# P27_v3.net
KiCad netlist of a schematic drawn in EAGLE
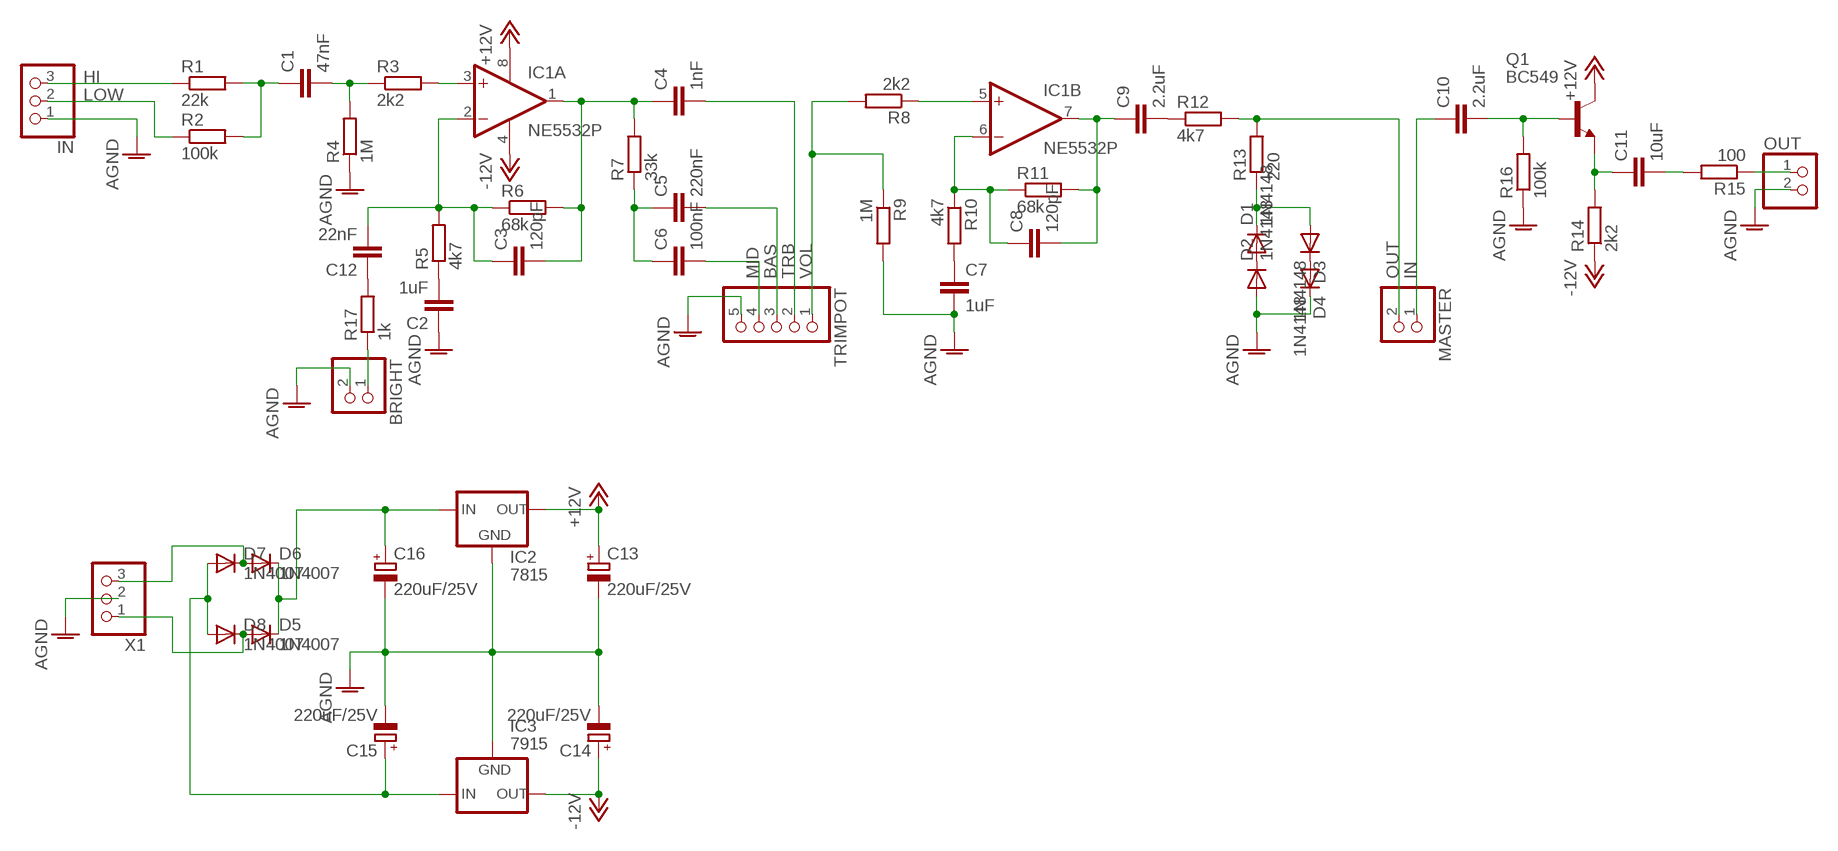
[diagram p0: schematic, sheet 1]

(export (version "E")
  (design (tool "Eeschema 10.0.6"))
  (components
    (comp (ref "BRIGHT")
      (value "PINHD-1X2")
      (footprint "eagle-import:1X02")
      (libsource (lib "eagle-import") (part "PINHD-1X2"))
    )
    (comp (ref "C1")
      (value "47nF")
      (footprint "eagle-import:C050-025X075")
      (libsource (lib "eagle-import") (part "C-EU050-025X075"))
    )
    (comp (ref "C2")
      (value "1uF")
      (footprint "eagle-import:C050-025X075")
      (libsource (lib "eagle-import") (part "C-EU050-025X075"))
    )
    (comp (ref "C3")
      (value "120pF")
      (footprint "eagle-import:C050-025X075")
      (libsource (lib "eagle-import") (part "C-EU050-025X075"))
    )
    (comp (ref "C4")
      (value "1nF")
      (footprint "eagle-import:C050-025X075")
      (libsource (lib "eagle-import") (part "C-EU050-025X075"))
    )
    (comp (ref "C5")
      (value "220nF")
      (footprint "eagle-import:C050-025X075")
      (libsource (lib "eagle-import") (part "C-EU050-025X075"))
    )
    (comp (ref "C6")
      (value "100nF")
      (footprint "eagle-import:C050-025X075")
      (libsource (lib "eagle-import") (part "C-EU050-025X075"))
    )
    (comp (ref "C7")
      (value "1uF")
      (footprint "eagle-import:C050-025X075")
      (libsource (lib "eagle-import") (part "C-EU050-025X075"))
    )
    (comp (ref "C8")
      (value "120pF")
      (footprint "eagle-import:C050-025X075")
      (libsource (lib "eagle-import") (part "C-EU050-025X075"))
    )
    (comp (ref "C9")
      (value "2.2uF")
      (footprint "eagle-import:C050-025X075")
      (libsource (lib "eagle-import") (part "C-EU050-025X075"))
    )
    (comp (ref "C10")
      (value "2.2uF")
      (footprint "eagle-import:C050-025X075")
      (libsource (lib "eagle-import") (part "C-EU050-025X075"))
    )
    (comp (ref "C11")
      (value "10uF")
      (footprint "eagle-import:C050-025X075")
      (libsource (lib "eagle-import") (part "C-EU050-025X075"))
    )
    (comp (ref "C12")
      (value "22nF")
      (footprint "eagle-import:C050-025X075")
      (libsource (lib "eagle-import") (part "C-EU050-025X075"))
    )
    (comp (ref "C13")
      (value "220uF/25V")
      (footprint "eagle-import:E2,5-6")
      (libsource (lib "eagle-import") (part "CPOL-EUE2.5-6"))
    )
    (comp (ref "C14")
      (value "220uF/25V")
      (footprint "eagle-import:E2,5-6")
      (libsource (lib "eagle-import") (part "CPOL-EUE2.5-6"))
    )
    (comp (ref "C15")
      (value "220uF/25V")
      (footprint "eagle-import:E2,5-6")
      (libsource (lib "eagle-import") (part "CPOL-EUE2.5-6"))
    )
    (comp (ref "C16")
      (value "220uF/25V")
      (footprint "eagle-import:E2,5-6")
      (libsource (lib "eagle-import") (part "CPOL-EUE2.5-6"))
    )
    (comp (ref "D1")
      (value "1N4148")
      (footprint "eagle-import:DO41-7")
      (libsource (lib "eagle-import") (part "1N4004D"))
    )
    (comp (ref "D2")
      (value "1N4148")
      (footprint "eagle-import:DO41-7")
      (libsource (lib "eagle-import") (part "1N4004D"))
    )
    (comp (ref "D3")
      (value "1N4148")
      (footprint "eagle-import:DO41-7")
      (libsource (lib "eagle-import") (part "1N4004D"))
    )
    (comp (ref "D4")
      (value "1N4148")
      (footprint "eagle-import:DO41-7")
      (libsource (lib "eagle-import") (part "1N4004D"))
    )
    (comp (ref "D5")
      (value "1N4007")
      (footprint "eagle-import:DO41-7")
      (libsource (lib "eagle-import") (part "1N4004D"))
    )
    (comp (ref "D6")
      (value "1N4007")
      (footprint "eagle-import:DO41-7")
      (libsource (lib "eagle-import") (part "1N4004D"))
    )
    (comp (ref "D7")
      (value "1N4007")
      (footprint "eagle-import:DO41-7")
      (libsource (lib "eagle-import") (part "1N4004D"))
    )
    (comp (ref "D8")
      (value "1N4007")
      (footprint "eagle-import:DO41-7")
      (libsource (lib "eagle-import") (part "1N4004D"))
    )
    (comp (ref "IC1")
      (value "NE5532P")
      (footprint "eagle-import:DIL08")
      (libsource (lib "eagle-import") (part "NE5532P"))
    )
    (comp (ref "IC2")
      (value "7815")
      (footprint "eagle-import:78XXS")
      (libsource (lib "eagle-import") (part "78XXTO-220"))
    )
    (comp (ref "IC3")
      (value "7915")
      (footprint "eagle-import:79XXS")
      (libsource (lib "eagle-import") (part "79XXTO-220"))
    )
    (comp (ref "IN")
      (value "PINHD-1X3180")
      (footprint "eagle-import:1X03")
      (libsource (lib "eagle-import") (part "PINHD-1X3180"))
    )
    (comp (ref "MASTER")
      (value "PINHD-1X2")
      (footprint "eagle-import:1X02")
      (libsource (lib "eagle-import") (part "PINHD-1X2"))
    )
    (comp (ref "OUT")
      (value "PINHD-1X2")
      (footprint "eagle-import:1X02")
      (libsource (lib "eagle-import") (part "PINHD-1X2"))
    )
    (comp (ref "Q1")
      (value "BC549")
      (footprint "eagle-import:TO92")
      (libsource (lib "eagle-import") (part "BC337"))
    )
    (comp (ref "R1")
      (value "22k")
      (footprint "eagle-import:0207_7")
      (libsource (lib "eagle-import") (part "R-EU_0207/7"))
    )
    (comp (ref "R2")
      (value "100k")
      (footprint "eagle-import:0207_7")
      (libsource (lib "eagle-import") (part "R-EU_0207/7"))
    )
    (comp (ref "R3")
      (value "2k2")
      (footprint "eagle-import:0207_7")
      (libsource (lib "eagle-import") (part "R-EU_0207/7"))
    )
    (comp (ref "R4")
      (value "1M")
      (footprint "eagle-import:0207_7")
      (libsource (lib "eagle-import") (part "R-EU_0207/7"))
    )
    (comp (ref "R5")
      (value "4k7")
      (footprint "eagle-import:0207_7")
      (libsource (lib "eagle-import") (part "R-EU_0207/7"))
    )
    (comp (ref "R6")
      (value "68k")
      (footprint "eagle-import:0207_7")
      (libsource (lib "eagle-import") (part "R-EU_0207/7"))
    )
    (comp (ref "R7")
      (value "33k")
      (footprint "eagle-import:0207_7")
      (libsource (lib "eagle-import") (part "R-EU_0207/7"))
    )
    (comp (ref "R8")
      (value "2k2")
      (footprint "eagle-import:0207_7")
      (libsource (lib "eagle-import") (part "R-EU_0207/7"))
    )
    (comp (ref "R9")
      (value "1M")
      (footprint "eagle-import:0207_7")
      (libsource (lib "eagle-import") (part "R-EU_0207/7"))
    )
    (comp (ref "R10")
      (value "4k7")
      (footprint "eagle-import:0207_7")
      (libsource (lib "eagle-import") (part "R-EU_0207/7"))
    )
    (comp (ref "R11")
      (value "68k")
      (footprint "eagle-import:0207_7")
      (libsource (lib "eagle-import") (part "R-EU_0207/7"))
    )
    (comp (ref "R12")
      (value "4k7")
      (footprint "eagle-import:0207_7")
      (libsource (lib "eagle-import") (part "R-EU_0207/7"))
    )
    (comp (ref "R13")
      (value "220")
      (footprint "eagle-import:0207_7")
      (libsource (lib "eagle-import") (part "R-EU_0207/7"))
    )
    (comp (ref "R14")
      (value "2k2")
      (footprint "eagle-import:0207_7")
      (libsource (lib "eagle-import") (part "R-EU_0207/7"))
    )
    (comp (ref "R15")
      (value "100")
      (footprint "eagle-import:0207_7")
      (libsource (lib "eagle-import") (part "R-EU_0207/7"))
    )
    (comp (ref "R16")
      (value "100k")
      (footprint "eagle-import:0207_7")
      (libsource (lib "eagle-import") (part "R-EU_0207/7"))
    )
    (comp (ref "R17")
      (value "1k")
      (footprint "eagle-import:0207_7")
      (libsource (lib "eagle-import") (part "R-EU_0207/7"))
    )
    (comp (ref "TRIMPOT")
      (value "PINHD-1X5")
      (footprint "eagle-import:1X05")
      (libsource (lib "eagle-import") (part "PINHD-1X5"))
    )
    (comp (ref "X1")
      (value "W237-103")
      (footprint "eagle-import:W237-103")
      (libsource (lib "eagle-import") (part "W237-103"))
    )
  )
  (nets
    (net (code "1") (name "+12V") (class "Default")
      (node (ref "C13") (pin "+") (pinfunction "+_+") (pintype "passive"))
      (node (ref "IC1") (pin "8") (pinfunction "V+_8") (pintype "power_in"))
      (node (ref "IC2") (pin "OUT") (pinfunction "OUT_OUT") (pintype "passive"))
      (node (ref "Q1") (pin "3") (pinfunction "C_3") (pintype "passive"))
    )
    (net (code "2") (name "-12V") (class "Default")
      (node (ref "C14") (pin "+") (pinfunction "+_+") (pintype "passive"))
      (node (ref "IC1") (pin "4") (pinfunction "V-_4") (pintype "power_in"))
      (node (ref "IC3") (pin "OUT") (pinfunction "OUT_OUT") (pintype "passive"))
      (node (ref "R14") (pin "1") (pinfunction "1_1") (pintype "passive"))
    )
    (net (code "3") (name "/BAS") (class "Default")
      (node (ref "C5") (pin "2") (pinfunction "2_2") (pintype "passive"))
      (node (ref "TRIMPOT") (pin "3") (pinfunction "3_3") (pintype "passive"))
    )
    (net (code "4") (name "/HI") (class "Default")
      (node (ref "IN") (pin "3") (pinfunction "3_3") (pintype "passive"))
      (node (ref "R1") (pin "1") (pinfunction "1_1") (pintype "passive"))
    )
    (net (code "5") (name "/IN") (class "Default")
      (node (ref "C10") (pin "1") (pinfunction "1_1") (pintype "passive"))
      (node (ref "MASTER") (pin "1") (pinfunction "1_1") (pintype "passive"))
    )
    (net (code "6") (name "/LOW") (class "Default")
      (node (ref "IN") (pin "2") (pinfunction "2_2") (pintype "passive"))
      (node (ref "R2") (pin "1") (pinfunction "1_1") (pintype "passive"))
    )
    (net (code "7") (name "/MID") (class "Default")
      (node (ref "C6") (pin "2") (pinfunction "2_2") (pintype "passive"))
      (node (ref "TRIMPOT") (pin "4") (pinfunction "4_4") (pintype "passive"))
    )
    (net (code "8") (name "/OUT") (class "Default")
      (node (ref "MASTER") (pin "2") (pinfunction "2_2") (pintype "passive"))
      (node (ref "R12") (pin "2") (pinfunction "2_2") (pintype "passive"))
      (node (ref "R13") (pin "2") (pinfunction "2_2") (pintype "passive"))
    )
    (net (code "9") (name "/TRB") (class "Default")
      (node (ref "C4") (pin "2") (pinfunction "2_2") (pintype "passive"))
      (node (ref "TRIMPOT") (pin "2") (pinfunction "2_2") (pintype "passive"))
    )
    (net (code "10") (name "/VOL") (class "Default")
      (node (ref "R8") (pin "2") (pinfunction "2_2") (pintype "passive"))
      (node (ref "R9") (pin "1") (pinfunction "1_1") (pintype "passive"))
      (node (ref "TRIMPOT") (pin "1") (pinfunction "1_1") (pintype "passive"))
    )
    (net (code "11") (name "AGND") (class "Default")
      (node (ref "BRIGHT") (pin "2") (pinfunction "2_2") (pintype "passive"))
      (node (ref "C13") (pin "-") (pinfunction "-_-") (pintype "passive"))
      (node (ref "C14") (pin "-") (pinfunction "-_-") (pintype "passive"))
      (node (ref "C15") (pin "-") (pinfunction "-_-") (pintype "passive"))
      (node (ref "C16") (pin "-") (pinfunction "-_-") (pintype "passive"))
      (node (ref "C2") (pin "1") (pinfunction "1_1") (pintype "passive"))
      (node (ref "C7") (pin "2") (pinfunction "2_2") (pintype "passive"))
      (node (ref "D2") (pin "A") (pinfunction "A_A") (pintype "passive"))
      (node (ref "D4") (pin "C") (pinfunction "C_C") (pintype "passive"))
      (node (ref "IC2") (pin "GND") (pinfunction "GND_GND") (pintype "input"))
      (node (ref "IC3") (pin "GND") (pinfunction "GND_GND") (pintype "input"))
      (node (ref "IN") (pin "1") (pinfunction "1_1") (pintype "passive"))
      (node (ref "OUT") (pin "2") (pinfunction "2_2") (pintype "passive"))
      (node (ref "R16") (pin "1") (pinfunction "1_1") (pintype "passive"))
      (node (ref "R4") (pin "1") (pinfunction "1_1") (pintype "passive"))
      (node (ref "R9") (pin "2") (pinfunction "2_2") (pintype "passive"))
      (node (ref "TRIMPOT") (pin "5") (pinfunction "5_5") (pintype "passive"))
      (node (ref "X1") (pin "2") (pinfunction "2_2") (pintype "passive"))
    )
    (net (code "12") (name "Net-(BRIGHT-Pad1)") (class "Default")
      (node (ref "BRIGHT") (pin "1") (pinfunction "1_1") (pintype "passive"))
      (node (ref "R17") (pin "1") (pinfunction "1_1") (pintype "passive"))
    )
    (net (code "13") (name "Net-(C1-Pad1)") (class "Default")
      (node (ref "C1") (pin "1") (pinfunction "1_1") (pintype "passive"))
      (node (ref "R1") (pin "2") (pinfunction "2_2") (pintype "passive"))
      (node (ref "R2") (pin "2") (pinfunction "2_2") (pintype "passive"))
    )
    (net (code "14") (name "Net-(C1-Pad2)") (class "Default")
      (node (ref "C1") (pin "2") (pinfunction "2_2") (pintype "passive"))
      (node (ref "R3") (pin "1") (pinfunction "1_1") (pintype "passive"))
      (node (ref "R4") (pin "2") (pinfunction "2_2") (pintype "passive"))
    )
    (net (code "15") (name "Net-(C2-Pad2)") (class "Default")
      (node (ref "C2") (pin "2") (pinfunction "2_2") (pintype "passive"))
      (node (ref "R5") (pin "1") (pinfunction "1_1") (pintype "passive"))
    )
    (net (code "16") (name "Net-(C5-Pad1)") (class "Default")
      (node (ref "C5") (pin "1") (pinfunction "1_1") (pintype "passive"))
      (node (ref "C6") (pin "1") (pinfunction "1_1") (pintype "passive"))
      (node (ref "R7") (pin "1") (pinfunction "1_1") (pintype "passive"))
    )
    (net (code "17") (name "Net-(C7-Pad1)") (class "Default")
      (node (ref "C7") (pin "1") (pinfunction "1_1") (pintype "passive"))
      (node (ref "R10") (pin "2") (pinfunction "2_2") (pintype "passive"))
    )
    (net (code "18") (name "Net-(C9-Pad2)") (class "Default")
      (node (ref "C9") (pin "2") (pinfunction "2_2") (pintype "passive"))
      (node (ref "R12") (pin "1") (pinfunction "1_1") (pintype "passive"))
    )
    (net (code "19") (name "Net-(C11-Pad2)") (class "Default")
      (node (ref "C11") (pin "2") (pinfunction "2_2") (pintype "passive"))
      (node (ref "R15") (pin "2") (pinfunction "2_2") (pintype "passive"))
    )
    (net (code "20") (name "Net-(C12-Pad1)") (class "Default")
      (node (ref "C12") (pin "1") (pinfunction "1_1") (pintype "passive"))
      (node (ref "R17") (pin "2") (pinfunction "2_2") (pintype "passive"))
    )
    (net (code "21") (name "Net-(C15-Pad+)") (class "Default")
      (node (ref "C15") (pin "+") (pinfunction "+_+") (pintype "passive"))
      (node (ref "D7") (pin "A") (pinfunction "A_A") (pintype "passive"))
      (node (ref "D8") (pin "A") (pinfunction "A_A") (pintype "passive"))
      (node (ref "IC3") (pin "IN") (pinfunction "IN_IN") (pintype "input"))
    )
    (net (code "22") (name "Net-(C16-Pad+)") (class "Default")
      (node (ref "C16") (pin "+") (pinfunction "+_+") (pintype "passive"))
      (node (ref "D5") (pin "C") (pinfunction "C_C") (pintype "passive"))
      (node (ref "D6") (pin "C") (pinfunction "C_C") (pintype "passive"))
      (node (ref "IC2") (pin "IN") (pinfunction "IN_IN") (pintype "input"))
    )
    (net (code "23") (name "Net-(D1-PadA)") (class "Default")
      (node (ref "D1") (pin "A") (pinfunction "A_A") (pintype "passive"))
      (node (ref "D2") (pin "C") (pinfunction "C_C") (pintype "passive"))
    )
    (net (code "24") (name "Net-(D1-PadC)") (class "Default")
      (node (ref "D1") (pin "C") (pinfunction "C_C") (pintype "passive"))
      (node (ref "D3") (pin "A") (pinfunction "A_A") (pintype "passive"))
      (node (ref "R13") (pin "1") (pinfunction "1_1") (pintype "passive"))
    )
    (net (code "25") (name "Net-(D3-PadC)") (class "Default")
      (node (ref "D3") (pin "C") (pinfunction "C_C") (pintype "passive"))
      (node (ref "D4") (pin "A") (pinfunction "A_A") (pintype "passive"))
    )
    (net (code "26") (name "Net-(D5-PadA)") (class "Default")
      (node (ref "D5") (pin "A") (pinfunction "A_A") (pintype "passive"))
      (node (ref "D8") (pin "C") (pinfunction "C_C") (pintype "passive"))
      (node (ref "X1") (pin "1") (pinfunction "1_1") (pintype "passive"))
    )
    (net (code "27") (name "Net-(D6-PadA)") (class "Default")
      (node (ref "D6") (pin "A") (pinfunction "A_A") (pintype "passive"))
      (node (ref "D7") (pin "C") (pinfunction "C_C") (pintype "passive"))
      (node (ref "X1") (pin "3") (pinfunction "3_3") (pintype "passive"))
    )
    (net (code "28") (name "Net-(IC1A-+IN)") (class "Default")
      (node (ref "IC1") (pin "3") (pinfunction "+IN_3") (pintype "input"))
      (node (ref "R3") (pin "2") (pinfunction "2_2") (pintype "passive"))
    )
    (net (code "29") (name "Net-(IC1A--IN)") (class "Default")
      (node (ref "C12") (pin "2") (pinfunction "2_2") (pintype "passive"))
      (node (ref "C3") (pin "1") (pinfunction "1_1") (pintype "passive"))
      (node (ref "IC1") (pin "2") (pinfunction "-IN_2") (pintype "input"))
      (node (ref "R5") (pin "2") (pinfunction "2_2") (pintype "passive"))
      (node (ref "R6") (pin "1") (pinfunction "1_1") (pintype "passive"))
    )
    (net (code "30") (name "Net-(IC1A-OUT)") (class "Default")
      (node (ref "C3") (pin "2") (pinfunction "2_2") (pintype "passive"))
      (node (ref "C4") (pin "1") (pinfunction "1_1") (pintype "passive"))
      (node (ref "IC1") (pin "1") (pinfunction "OUT_1") (pintype "output"))
      (node (ref "R6") (pin "2") (pinfunction "2_2") (pintype "passive"))
      (node (ref "R7") (pin "2") (pinfunction "2_2") (pintype "passive"))
    )
    (net (code "31") (name "Net-(IC1B-+IN)") (class "Default")
      (node (ref "IC1") (pin "5") (pinfunction "+IN_5") (pintype "input"))
      (node (ref "R8") (pin "1") (pinfunction "1_1") (pintype "passive"))
    )
    (net (code "32") (name "Net-(IC1B--IN)") (class "Default")
      (node (ref "C8") (pin "1") (pinfunction "1_1") (pintype "passive"))
      (node (ref "IC1") (pin "6") (pinfunction "-IN_6") (pintype "input"))
      (node (ref "R10") (pin "1") (pinfunction "1_1") (pintype "passive"))
      (node (ref "R11") (pin "1") (pinfunction "1_1") (pintype "passive"))
    )
    (net (code "33") (name "Net-(IC1B-OUT)") (class "Default")
      (node (ref "C8") (pin "2") (pinfunction "2_2") (pintype "passive"))
      (node (ref "C9") (pin "1") (pinfunction "1_1") (pintype "passive"))
      (node (ref "IC1") (pin "7") (pinfunction "OUT_7") (pintype "output"))
      (node (ref "R11") (pin "2") (pinfunction "2_2") (pintype "passive"))
    )
    (net (code "34") (name "Net-(OUT-Pad1)") (class "Default")
      (node (ref "OUT") (pin "1") (pinfunction "1_1") (pintype "passive"))
      (node (ref "R15") (pin "1") (pinfunction "1_1") (pintype "passive"))
    )
    (net (code "35") (name "Net-(Q1-B)") (class "Default")
      (node (ref "C10") (pin "2") (pinfunction "2_2") (pintype "passive"))
      (node (ref "Q1") (pin "2") (pinfunction "B_2") (pintype "passive"))
      (node (ref "R16") (pin "2") (pinfunction "2_2") (pintype "passive"))
    )
    (net (code "36") (name "Net-(Q1-E)") (class "Default")
      (node (ref "C11") (pin "1") (pinfunction "1_1") (pintype "passive"))
      (node (ref "Q1") (pin "1") (pinfunction "E_1") (pintype "passive"))
      (node (ref "R14") (pin "2") (pinfunction "2_2") (pintype "passive"))
    )
  )
)
